# PDM_Mk21_-_Mini.net
KiCad netlist of a schematic drawn in Altium Designer
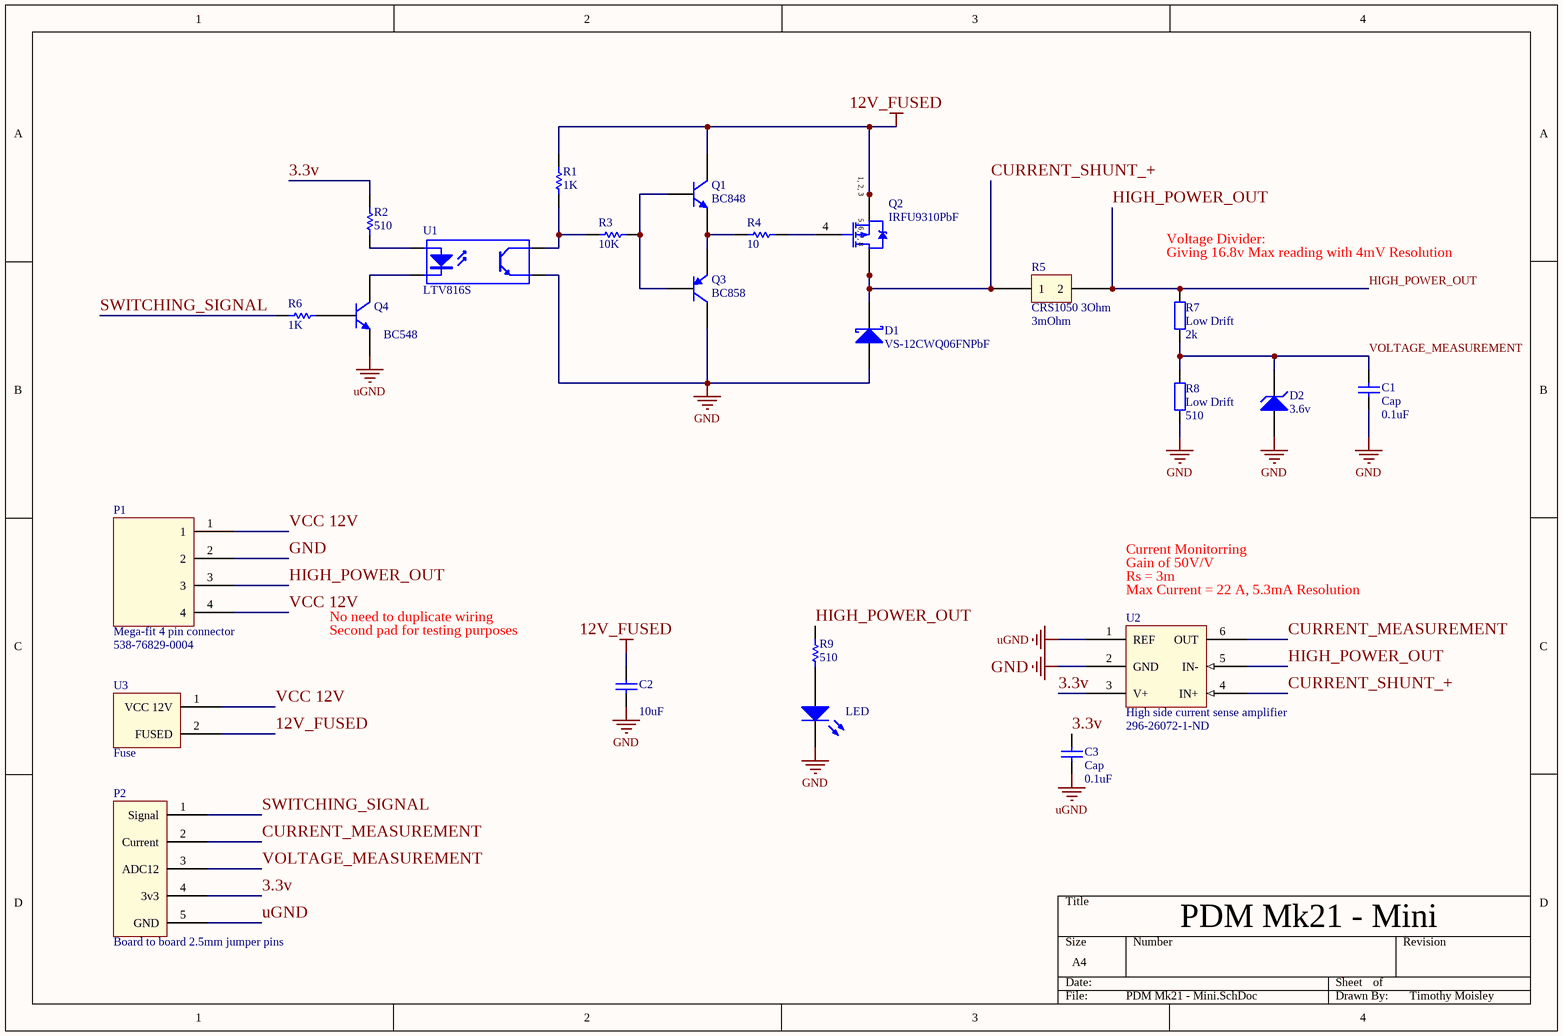
[diagram p0: PDM Mk21 - Mini.SchDoc]

(export (version "E")
  (design (tool "Eeschema 10.0.6"))
  (components
    (comp (ref "C1")
      (value "Cap")
      (footprint "C0805")
      (description "Capacitor")
      (fields (field (name "ALTIUM_VALUE") "0.1uF") (field (name "PUBLISHER") "Altium Limited"))
      (libsource (lib "Miscellaneous Devices") (part "Cap"))
    )
    (comp (ref "C2")
      (value "10uF")
      (footprint "C0805")
      (description "Capacitor")
      (fields (field (name "MANUFACTURER PART NO.") "490-5523-1-ND") (field (name "Comment") "Cap"))
      (libsource (lib "Miscellaneous Devices") (part "Cap"))
    )
    (comp (ref "C3")
      (value "Cap")
      (footprint "C0805")
      (description "Capacitor")
      (fields (field (name "ALTIUM_VALUE") "0.1uF") (field (name "PUBLISHER") "Altium Limited"))
      (libsource (lib "Miscellaneous Devices") (part "Cap"))
    )
    (comp (ref "D1")
      (value "VS-12CWQ06FNPbF")
      (footprint "DPAK")
      (description "Schottky Rectifier")
      (fields (field (name "PUBLISHER") "Altium Limited"))
      (libsource (lib "IR Rectifier - Schottky") (part "MBR1645"))
    )
    (comp (ref "D2")
      (value "3.6v")
      (footprint "BZX84CxxxET1G")
      (description "Zener Diode")
      (fields (field (name "PUBLISHER") "Altium Limited"))
      (libsource (lib "Miscellaneous Devices") (part "D Zener"))
    )
    (comp (ref "LED")
      (value "~")
      (footprint "LED-0")
      (description "Typical INFRARED GaAs LED")
      (fields (field (name "PUBLISHER") "Altium Limited"))
      (libsource (lib "Miscellaneous Devices") (part "LED0"))
    )
    (comp (ref "P1")
      (value "Mega-fit 4 pin connector")
      (footprint "Mega-fit 4 pin connector")
      (description "MOLEX mega-fit 4 pin connector")
      (fields
        (field (name "MANUFACTURER") "MOLEX")
        (field (name "MANUFACTURER PART NO.") "76829-0004")
        (field (name "SUPPLIER PART NO.") "538-76829-0004")
      )
      (libsource (lib "PDM Mk21 - Mini") (part "Mega-fit 4 pin connector"))
    )
    (comp (ref "P2")
      (value "Board to board 2.5mm jumper pins")
      (footprint "Board-Board Jumper")
      (libsource (lib "PDM Mk21 - Mini") (part "Board-Board Jumper"))
    )
    (comp (ref "Q1")
      (value "BC848")
      (footprint "SOT-23_L")
      (description "NPN General Purpose Amplifier")
      (fields (field (name "PUBLISHER") "Altium Limited"))
      (libsource (lib "FSC Discrete BJT") (part "BC817-25"))
    )
    (comp (ref "Q2")
      (value "IRFU9310PbF")
      (footprint "SO8_N")
      (description "HEXFET Power MOSFET - International Rectifier")
      (fields (field (name "PUBLISHER") "Altium Limited"))
      (libsource (lib "IR Discrete MOSFET - Power") (part "IRF7220"))
    )
    (comp (ref "Q3")
      (value "BC858")
      (footprint "SOT-23_L")
      (description "PNP General Purpose Amplifier")
      (fields (field (name "PUBLISHER") "Altium Limited"))
      (libsource (lib "FSC Discrete BJT") (part "BC807-16"))
    )
    (comp (ref "Q4")
      (value "BC548")
      (footprint "SOT-23_L")
      (description "NPN General Purpose Amplifier")
      (fields (field (name "MANUFACTURER PART NO.") "CRS1050 R003") (field (name "Comment") "NPN"))
      (libsource (lib "FSC Discrete BJT") (part "BC817-25"))
    )
    (comp (ref "R1")
      (value "1K")
      (footprint "C0805")
      (description "Resistor")
      (fields (field (name "Comment") "GND") (field (name "PUBLISHER") "Altium Limited"))
      (libsource (lib "Miscellaneous Devices") (part "Res1"))
    )
    (comp (ref "R2")
      (value "510")
      (footprint "C0805")
      (description "Resistor")
      (fields (field (name "Comment") "GND") (field (name "PUBLISHER") "Altium Limited"))
      (libsource (lib "Miscellaneous Devices") (part "Res1"))
    )
    (comp (ref "R3")
      (value "10K")
      (footprint "C0805")
      (description "Resistor")
      (fields (field (name "Comment") "GND") (field (name "PUBLISHER") "Altium Limited"))
      (libsource (lib "Miscellaneous Devices") (part "Res1"))
    )
    (comp (ref "R4")
      (value "10")
      (footprint "C0805")
      (description "Resistor")
      (fields (field (name "Comment") "Res1") (field (name "PUBLISHER") "Altium Limited"))
      (libsource (lib "Miscellaneous Devices") (part "Res1"))
    )
    (comp (ref "R5")
      (value "CRS1050 3Ohm")
      (footprint "CRS1050")
      (description "Current Shunt Resistor")
      (fields (field (name "MANUFACTURER PART NO.") "CRS1050 R003") (field (name "ALTIUM_VALUE") "3mOhm"))
      (libsource (lib "PDM Mk21 - Mini") (part "CSR1050"))
    )
    (comp (ref "R6")
      (value "1K")
      (footprint "C0805")
      (description "Resistor")
      (fields (field (name "Comment") "IN") (field (name "PUBLISHER") "Altium Limited"))
      (libsource (lib "Miscellaneous Devices") (part "Res1"))
    )
    (comp (ref "R7")
      (value "Low Drift")
      (footprint "R0805")
      (description "Resistor")
      (fields (field (name "ALTIUM_VALUE") "2k") (field (name "PUBLISHER") "Altium Limited"))
      (libsource (lib "Miscellaneous Devices") (part "Res2"))
    )
    (comp (ref "R8")
      (value "Low Drift")
      (footprint "R0805")
      (description "Resistor")
      (fields (field (name "ALTIUM_VALUE") "510") (field (name "PUBLISHER") "Altium Limited"))
      (libsource (lib "Miscellaneous Devices") (part "Res2"))
    )
    (comp (ref "R9")
      (value "510")
      (footprint "C0805")
      (description "Resistor")
      (fields (field (name "Comment") "GND") (field (name "PUBLISHER") "Altium Limited"))
      (libsource (lib "Miscellaneous Devices") (part "Res1"))
    )
    (comp (ref "U1")
      (value "LTV816S")
      (footprint "DIP-4")
      (description "4-Pin Phototransistor Optocoupler")
      (fields
        (field (name "MANUFACTURER PART NUMBER") "LTV-816S")
        (field (name "PART NUMBER") "859-LTV-816S")
        (field (name "PUBLISHER") "Altium Limited")
      )
      (libsource (lib "Miscellaneous Devices") (part "Optoisolator1"))
    )
    (comp (ref "U2")
      (value "High side current sense amplifier")
      (footprint "INA212")
      (fields
        (field (name "MANUFACTURER") "Texas Instruments")
        (field (name "MANUFACTURER PART NO.") "INA212CIDCKR")
        (field (name "SUPPLIER PART NUMBER") "296-26072-1-ND")
      )
      (libsource (lib "PDM Mk21 - Mini") (part "INA212"))
    )
    (comp (ref "U3") (value "Fuse") (footprint "Fuse") (libsource (lib "PDM Mk21 - Mini") (part "Fuse")))
  )
  (nets
    (net (code "1") (name "/3.3v") (class "Default")
      (node (ref "C3") (pin "2") (pinfunction "2_2") (pintype "passive"))
      (node (ref "P2") (pin "4") (pinfunction "3v3_4") (pintype "passive"))
      (node (ref "R2") (pin "1") (pinfunction "1_1") (pintype "passive"))
      (node (ref "U2") (pin "3") (pinfunction "V+_3") (pintype "passive"))
    )
    (net (code "2") (name "/CURRENT_MEASUREMENT") (class "Default")
      (node (ref "P2") (pin "2") (pinfunction "Current_2") (pintype "passive"))
      (node (ref "U2") (pin "6") (pinfunction "OUT_6") (pintype "passive"))
    )
    (net (code "3") (name "/CURRENT_SHUNT_+") (class "Default")
      (node (ref "D1") (pin "1") (pinfunction "K_1") (pintype "passive"))
      (node (ref "Q2") (pin "5") (pinfunction "D_5") (pintype "passive"))
      (node (ref "Q2") (pin "6") (pinfunction "D_6") (pintype "passive"))
      (node (ref "Q2") (pin "7") (pinfunction "D_7") (pintype "passive"))
      (node (ref "Q2") (pin "8") (pinfunction "D_8") (pintype "passive"))
      (node (ref "R5") (pin "1") (pinfunction "1_1") (pintype "passive"))
      (node (ref "U2") (pin "4") (pinfunction "IN+_4") (pintype "input"))
    )
    (net (code "4") (name "/HIGH_POWER_OUT") (class "Default")
      (node (ref "P1") (pin "3") (pinfunction "3_3") (pintype "passive"))
      (node (ref "R5") (pin "2") (pinfunction "2_2") (pintype "passive"))
      (node (ref "R7") (pin "2") (pinfunction "2_2") (pintype "passive"))
      (node (ref "R9") (pin "1") (pinfunction "1_1") (pintype "passive"))
      (node (ref "U2") (pin "5") (pinfunction "IN-_5") (pintype "input"))
    )
    (net (code "5") (name "/SWITCHING_SIGNAL") (class "Default")
      (node (ref "P2") (pin "1") (pinfunction "Signal_1") (pintype "passive"))
      (node (ref "R6") (pin "1") (pinfunction "1_1") (pintype "passive"))
    )
    (net (code "6") (name "/VCC 12V") (class "Default")
      (node (ref "P1") (pin "1") (pinfunction "1_1") (pintype "passive"))
      (node (ref "P1") (pin "4") (pinfunction "4_4") (pintype "passive"))
      (node (ref "U3") (pin "1") (pinfunction "VCC_12V_1") (pintype "passive"))
    )
    (net (code "7") (name "/VOLTAGE_MEASUREMENT") (class "Default")
      (node (ref "C1") (pin "2") (pinfunction "2_2") (pintype "passive"))
      (node (ref "D2") (pin "2") (pinfunction "K_2") (pintype "passive"))
      (node (ref "P2") (pin "3") (pinfunction "ADC12_3") (pintype "passive"))
      (node (ref "R7") (pin "1") (pinfunction "1_1") (pintype "passive"))
      (node (ref "R8") (pin "2") (pinfunction "2_2") (pintype "passive"))
    )
    (net (code "8") (name "12V_FUSED") (class "Default")
      (node (ref "C2") (pin "2") (pinfunction "2_2") (pintype "passive"))
      (node (ref "Q1") (pin "3") (pinfunction "C_3") (pintype "passive"))
      (node (ref "Q2") (pin "1") (pinfunction "S_1") (pintype "passive"))
      (node (ref "Q2") (pin "2") (pinfunction "S_2") (pintype "passive"))
      (node (ref "Q2") (pin "3") (pinfunction "S_3") (pintype "passive"))
      (node (ref "R1") (pin "1") (pinfunction "1_1") (pintype "passive"))
      (node (ref "U3") (pin "2") (pinfunction "FUSED_2") (pintype "passive"))
    )
    (net (code "9") (name "GND") (class "Default")
      (node (ref "C1") (pin "1") (pinfunction "1_1") (pintype "passive"))
      (node (ref "C2") (pin "1") (pinfunction "1_1") (pintype "passive"))
      (node (ref "D1") (pin "3") (pinfunction "A_3") (pintype "passive"))
      (node (ref "D2") (pin "1") (pinfunction "A_1") (pintype "passive"))
      (node (ref "LED") (pin "2") (pinfunction "K_2") (pintype "passive"))
      (node (ref "P1") (pin "2") (pinfunction "2_2") (pintype "passive"))
      (node (ref "Q3") (pin "3") (pinfunction "C_3") (pintype "passive"))
      (node (ref "R8") (pin "1") (pinfunction "1_1") (pintype "passive"))
      (node (ref "U1") (pin "3") (pinfunction "E_3") (pintype "passive"))
      (node (ref "U2") (pin "2") (pinfunction "GND_2") (pintype "passive"))
    )
    (net (code "10") (name "Net-(LED-A)") (class "Default")
      (node (ref "LED") (pin "1") (pinfunction "A_1") (pintype "passive"))
      (node (ref "R9") (pin "2") (pinfunction "2_2") (pintype "passive"))
    )
    (net (code "11") (name "Net-(Q1-B)") (class "Default")
      (node (ref "Q1") (pin "1") (pinfunction "B_1") (pintype "passive"))
      (node (ref "Q3") (pin "1") (pinfunction "B_1") (pintype "passive"))
      (node (ref "R3") (pin "2") (pinfunction "2_2") (pintype "passive"))
    )
    (net (code "12") (name "Net-(Q1-E)") (class "Default")
      (node (ref "Q1") (pin "2") (pinfunction "E_2") (pintype "passive"))
      (node (ref "Q3") (pin "2") (pinfunction "E_2") (pintype "passive"))
      (node (ref "R4") (pin "1") (pinfunction "1_1") (pintype "passive"))
    )
    (net (code "13") (name "Net-(Q2-G)") (class "Default")
      (node (ref "Q2") (pin "4") (pinfunction "G_4") (pintype "passive"))
      (node (ref "R4") (pin "2") (pinfunction "2_2") (pintype "passive"))
    )
    (net (code "14") (name "Net-(Q4-B)") (class "Default")
      (node (ref "Q4") (pin "1") (pinfunction "B_1") (pintype "passive"))
      (node (ref "R6") (pin "2") (pinfunction "2_2") (pintype "passive"))
    )
    (net (code "15") (name "Net-(Q4-C)") (class "Default")
      (node (ref "Q4") (pin "3") (pinfunction "C_3") (pintype "passive"))
      (node (ref "U1") (pin "2") (pinfunction "K_2") (pintype "passive"))
    )
    (net (code "16") (name "Net-(U1-A)") (class "Default")
      (node (ref "R2") (pin "2") (pinfunction "2_2") (pintype "passive"))
      (node (ref "U1") (pin "1") (pinfunction "A_1") (pintype "passive"))
    )
    (net (code "17") (name "Net-(U1-C)") (class "Default")
      (node (ref "R1") (pin "2") (pinfunction "2_2") (pintype "passive"))
      (node (ref "R3") (pin "1") (pinfunction "1_1") (pintype "passive"))
      (node (ref "U1") (pin "4") (pinfunction "C_4") (pintype "passive"))
    )
    (net (code "18") (name "uGND") (class "Default")
      (node (ref "C3") (pin "1") (pinfunction "1_1") (pintype "passive"))
      (node (ref "P2") (pin "5") (pinfunction "GND_5") (pintype "passive"))
      (node (ref "Q4") (pin "2") (pinfunction "E_2") (pintype "passive"))
      (node (ref "U2") (pin "1") (pinfunction "REF_1") (pintype "passive"))
    )
  )
)
